# I2C_Peripherals.net
KiCad netlist of a schematic drawn in Altium Designer
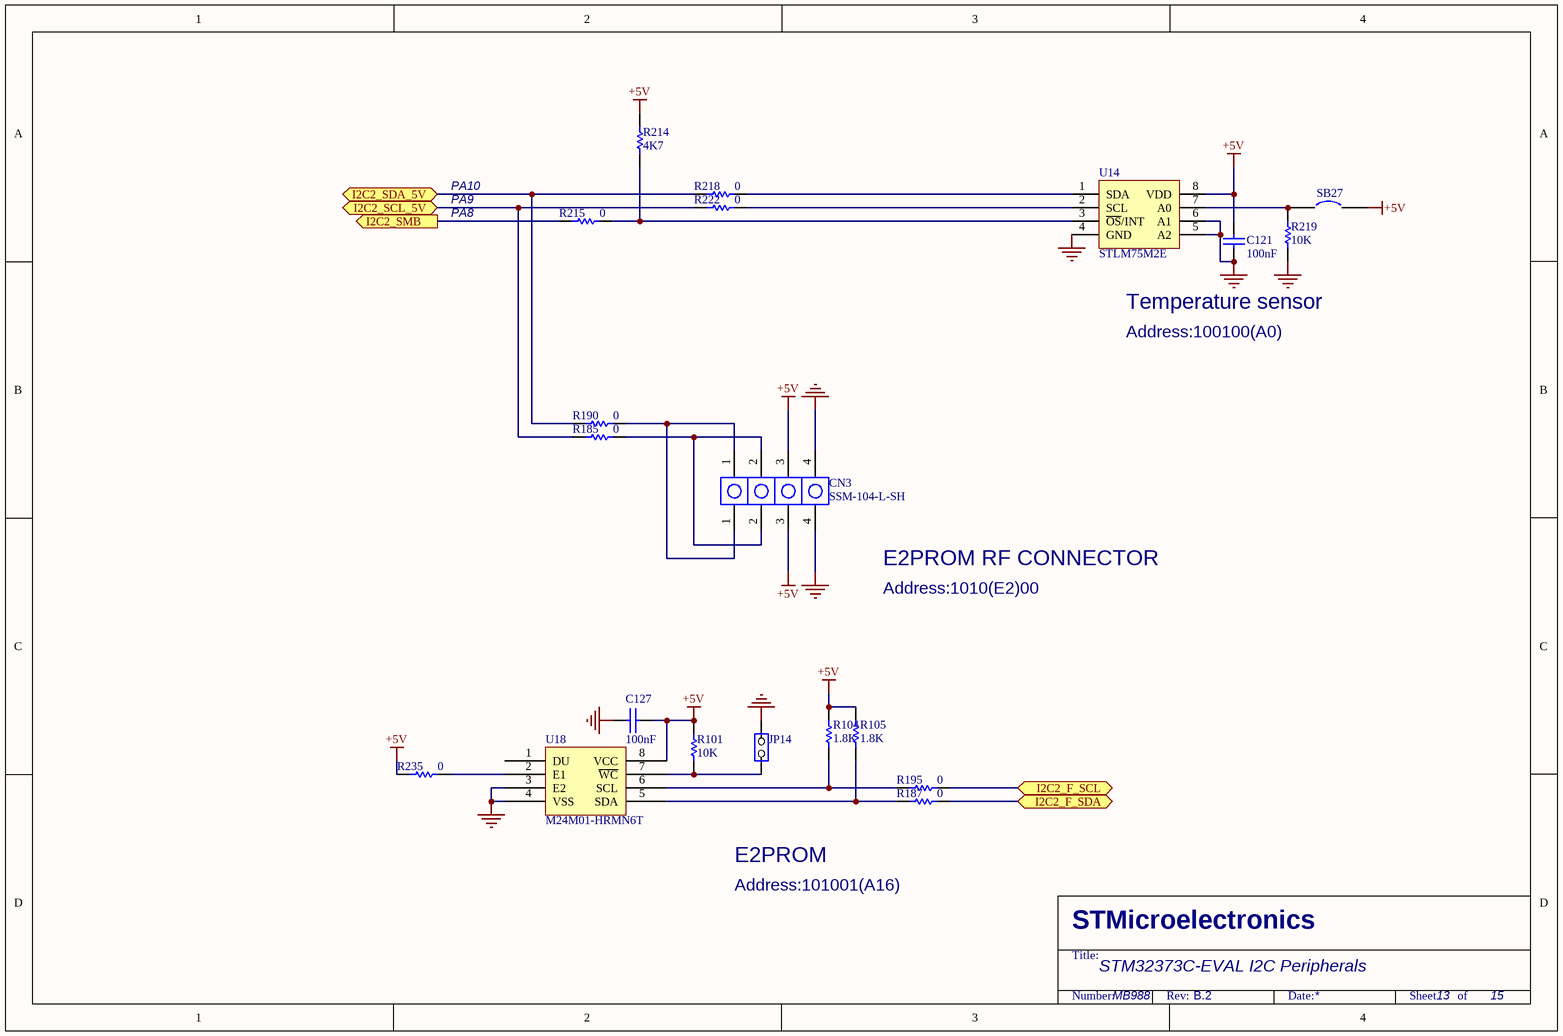
[diagram p0: I2C Peripherals.SCHDOC]

(export (version "E")
  (design (tool "Eeschema 10.0.6"))
  (components
    (comp (ref "C121")
      (value "100nF")
      (footprint "0603C")
      (description "Capacitor")
      (fields (field (name "PUBLISHER") "Altium Limited"))
      (libsource (lib "Miscellaneous Devices") (part "cap"))
    )
    (comp (ref "C127")
      (value "100nF")
      (footprint "0603C")
      (description "Capacitor")
      (libsource (lib "*") (part "CAP"))
    )
    (comp (ref "CN3")
      (value "SSM-104-L-SH")
      (footprint "SSM-104-L-SH")
      (libsource (lib "MB964") (part "SSM-104-L-SH"))
    )
    (comp (ref "JP14") (value "~") (footprint "SIP2") (libsource (lib "*") (part "JP2")))
    (comp (ref "R101")
      (value "10K")
      (footprint "0603R")
      (description "Resistor")
      (fields (field (name "PUBLISHER") "Altium Limited"))
      (libsource (lib "Miscellaneous Devices") (part "res1"))
    )
    (comp (ref "R104")
      (value "1.8K")
      (footprint "0603R")
      (description "Resistor")
      (fields (field (name "PUBLISHER") "Altium Limited"))
      (libsource (lib "Miscellaneous Devices") (part "Res1"))
    )
    (comp (ref "R105")
      (value "1.8K")
      (footprint "0603R")
      (description "Resistor")
      (fields (field (name "PUBLISHER") "Altium Limited"))
      (libsource (lib "Miscellaneous Devices") (part "Res1"))
    )
    (comp (ref "R185")
      (value "0")
      (footprint "0603R")
      (description "Resistor")
      (fields (field (name "PUBLISHER") "Altium Limited"))
      (libsource (lib "Miscellaneous Devices") (part "Res1"))
    )
    (comp (ref "R187")
      (value "0")
      (footprint "0603R")
      (description "Resistor")
      (fields (field (name "PUBLISHER") "Altium Limited"))
      (libsource (lib "Miscellaneous Devices") (part "Res1"))
    )
    (comp (ref "R190")
      (value "0")
      (footprint "0603R")
      (description "Resistor")
      (fields (field (name "PUBLISHER") "Altium Limited"))
      (libsource (lib "Miscellaneous Devices") (part "Res1"))
    )
    (comp (ref "R195")
      (value "0")
      (footprint "0603R")
      (description "Resistor")
      (fields (field (name "PUBLISHER") "Altium Limited"))
      (libsource (lib "Miscellaneous Devices") (part "Res1"))
    )
    (comp (ref "R214")
      (value "4K7")
      (footprint "0603R")
      (description "Resistor")
      (fields (field (name "PUBLISHER") "Altium Limited"))
      (libsource (lib "Miscellaneous Devices") (part "Res1"))
    )
    (comp (ref "R215")
      (value "0")
      (footprint "0603R")
      (description "Resistor")
      (fields (field (name "PUBLISHER") "Altium Limited"))
      (libsource (lib "Miscellaneous Devices") (part "Res1"))
    )
    (comp (ref "R218")
      (value "0")
      (footprint "0603R")
      (description "Resistor")
      (fields (field (name "PUBLISHER") "Altium Limited"))
      (libsource (lib "Miscellaneous Devices") (part "Res1"))
    )
    (comp (ref "R219")
      (value "10K")
      (footprint "0603R")
      (description "Resistor")
      (fields (field (name "PUBLISHER") "Altium Limited"))
      (libsource (lib "Miscellaneous Devices") (part "Res1"))
    )
    (comp (ref "R222")
      (value "0")
      (footprint "0603R")
      (description "Resistor")
      (fields (field (name "PUBLISHER") "Altium Limited"))
      (libsource (lib "Miscellaneous Devices") (part "Res1"))
    )
    (comp (ref "R235")
      (value "0")
      (footprint "0603R")
      (description "Resistor")
      (fields (field (name "PUBLISHER") "Altium Limited"))
      (libsource (lib "Miscellaneous Devices") (part "Res1"))
    )
    (comp (ref "SB27")
      (value "~")
      (footprint "JP2_SMD")
      (description "Circuit Breaker")
      (fields (field (name "PUBLISHER") "Altium Limited"))
      (libsource (lib "Miscellaneous Devices") (part "Circuit Breaker"))
    )
    (comp (ref "U14") (value "STLM75M2E") (footprint "SO8") (libsource (lib "MB525") (part "STLM75DW2F")))
    (comp (ref "U18") (value "M24M01-HRMN6T") (footprint "SO8") (libsource (lib "MB988") (part "M24M01")))
  )
  (nets
    (net (code "1") (name "+5V") (class "Default")
      (node (ref "C121") (pin "2") (pinfunction "2_2") (pintype "passive"))
      (node (ref "C127") (pin "2") (pinfunction "2_2") (pintype "passive"))
      (node (ref "CN3") (pin "3") (pinfunction "3_3") (pintype "passive"))
      (node (ref "R101") (pin "1") (pinfunction "1_1") (pintype "passive"))
      (node (ref "R104") (pin "2") (pinfunction "2_2") (pintype "passive"))
      (node (ref "R105") (pin "2") (pinfunction "2_2") (pintype "passive"))
      (node (ref "R214") (pin "2") (pinfunction "2_2") (pintype "passive"))
      (node (ref "R235") (pin "1") (pinfunction "1_1") (pintype "passive"))
      (node (ref "SB27") (pin "2") (pinfunction "2_2") (pintype "passive"))
      (node (ref "U14") (pin "8") (pinfunction "VDD_8") (pintype "passive"))
      (node (ref "U18") (pin "8") (pinfunction "VCC_8") (pintype "passive"))
    )
    (net (code "2") (name "/I2C2_F_SCL") (class "Default")
      (node (ref "R195") (pin "2") (pinfunction "2_2") (pintype "passive"))
    )
    (net (code "3") (name "/I2C2_F_SDA") (class "Default")
      (node (ref "R187") (pin "2") (pinfunction "2_2") (pintype "passive"))
    )
    (net (code "4") (name "/I2C2_SCL_5V") (class "Default")
      (node (ref "R185") (pin "1") (pinfunction "1_1") (pintype "passive"))
      (node (ref "R222") (pin "1") (pinfunction "1_1") (pintype "passive"))
    )
    (net (code "5") (name "/I2C2_SDA_5V") (class "Default")
      (node (ref "R190") (pin "1") (pinfunction "1_1") (pintype "passive"))
      (node (ref "R218") (pin "1") (pinfunction "1_1") (pintype "passive"))
    )
    (net (code "6") (name "/I2C2_SMB") (class "Default")
      (node (ref "R215") (pin "2") (pinfunction "2_2") (pintype "passive"))
    )
    (net (code "7") (name "GND") (class "Default")
      (node (ref "C121") (pin "1") (pinfunction "1_1") (pintype "passive"))
      (node (ref "C127") (pin "1") (pinfunction "1_1") (pintype "passive"))
      (node (ref "CN3") (pin "4") (pinfunction "4_4") (pintype "passive"))
      (node (ref "JP14") (pin "2") (pinfunction "NO_2") (pintype "passive"))
      (node (ref "R219") (pin "1") (pinfunction "1_1") (pintype "passive"))
      (node (ref "U14") (pin "4") (pinfunction "GND_4") (pintype "passive"))
      (node (ref "U14") (pin "5") (pinfunction "A2_5") (pintype "passive"))
      (node (ref "U14") (pin "6") (pinfunction "A1_6") (pintype "passive"))
      (node (ref "U18") (pin "3") (pinfunction "E2_3") (pintype "passive"))
      (node (ref "U18") (pin "4") (pinfunction "VSS_4") (pintype "passive"))
    )
    (net (code "8") (name "Net-(CN3-Pad1)") (class "Default")
      (node (ref "CN3") (pin "1") (pinfunction "1_1") (pintype "passive"))
      (node (ref "R190") (pin "2") (pinfunction "2_2") (pintype "passive"))
    )
    (net (code "9") (name "Net-(CN3-Pad2)") (class "Default")
      (node (ref "CN3") (pin "2") (pinfunction "2_2") (pintype "passive"))
      (node (ref "R185") (pin "2") (pinfunction "2_2") (pintype "passive"))
    )
    (net (code "10") (name "Net-(JP14-COMMON)") (class "Default")
      (node (ref "JP14") (pin "1") (pinfunction "COMMON_1") (pintype "passive"))
      (node (ref "R101") (pin "2") (pinfunction "2_2") (pintype "passive"))
      (node (ref "U18") (pin "7") (pinfunction "~{WC}_7") (pintype "passive"))
    )
    (net (code "11") (name "Net-(U14-A0)") (class "Default")
      (node (ref "R219") (pin "2") (pinfunction "2_2") (pintype "passive"))
      (node (ref "SB27") (pin "1") (pinfunction "1_1") (pintype "passive"))
      (node (ref "U14") (pin "7") (pinfunction "A0_7") (pintype "passive"))
    )
    (net (code "12") (name "Net-(U14-SCL)") (class "Default")
      (node (ref "R222") (pin "2") (pinfunction "2_2") (pintype "passive"))
      (node (ref "U14") (pin "2") (pinfunction "SCL_2") (pintype "passive"))
    )
    (net (code "13") (name "Net-(U14-SDA)") (class "Default")
      (node (ref "R218") (pin "2") (pinfunction "2_2") (pintype "passive"))
      (node (ref "U14") (pin "1") (pinfunction "SDA_1") (pintype "passive"))
    )
    (net (code "14") (name "Net-(U14-~{OS}{slash}INT)") (class "Default")
      (node (ref "R214") (pin "1") (pinfunction "1_1") (pintype "passive"))
      (node (ref "R215") (pin "1") (pinfunction "1_1") (pintype "passive"))
      (node (ref "U14") (pin "3") (pinfunction "~{OS}/INT_3") (pintype "passive"))
    )
    (net (code "15") (name "Net-(U18-E1)") (class "Default")
      (node (ref "R235") (pin "2") (pinfunction "2_2") (pintype "passive"))
      (node (ref "U18") (pin "2") (pinfunction "E1_2") (pintype "passive"))
    )
    (net (code "16") (name "Net-(U18-SCL)") (class "Default")
      (node (ref "R104") (pin "1") (pinfunction "1_1") (pintype "passive"))
      (node (ref "R195") (pin "1") (pinfunction "1_1") (pintype "passive"))
      (node (ref "U18") (pin "6") (pinfunction "SCL_6") (pintype "passive"))
    )
    (net (code "17") (name "Net-(U18-SDA)") (class "Default")
      (node (ref "R105") (pin "1") (pinfunction "1_1") (pintype "passive"))
      (node (ref "R187") (pin "1") (pinfunction "1_1") (pintype "passive"))
      (node (ref "U18") (pin "5") (pinfunction "SDA_5") (pintype "passive"))
    )
    (net (code "18") (name "unconnected-(U18-DU-Pad1)") (class "Default")
      (node (ref "U18") (pin "1") (pinfunction "DU_1") (pintype "passive"))
    )
  )
)
